# EsquematicoFonte.net
KiCad netlist of a schematic drawn in Altium Designer
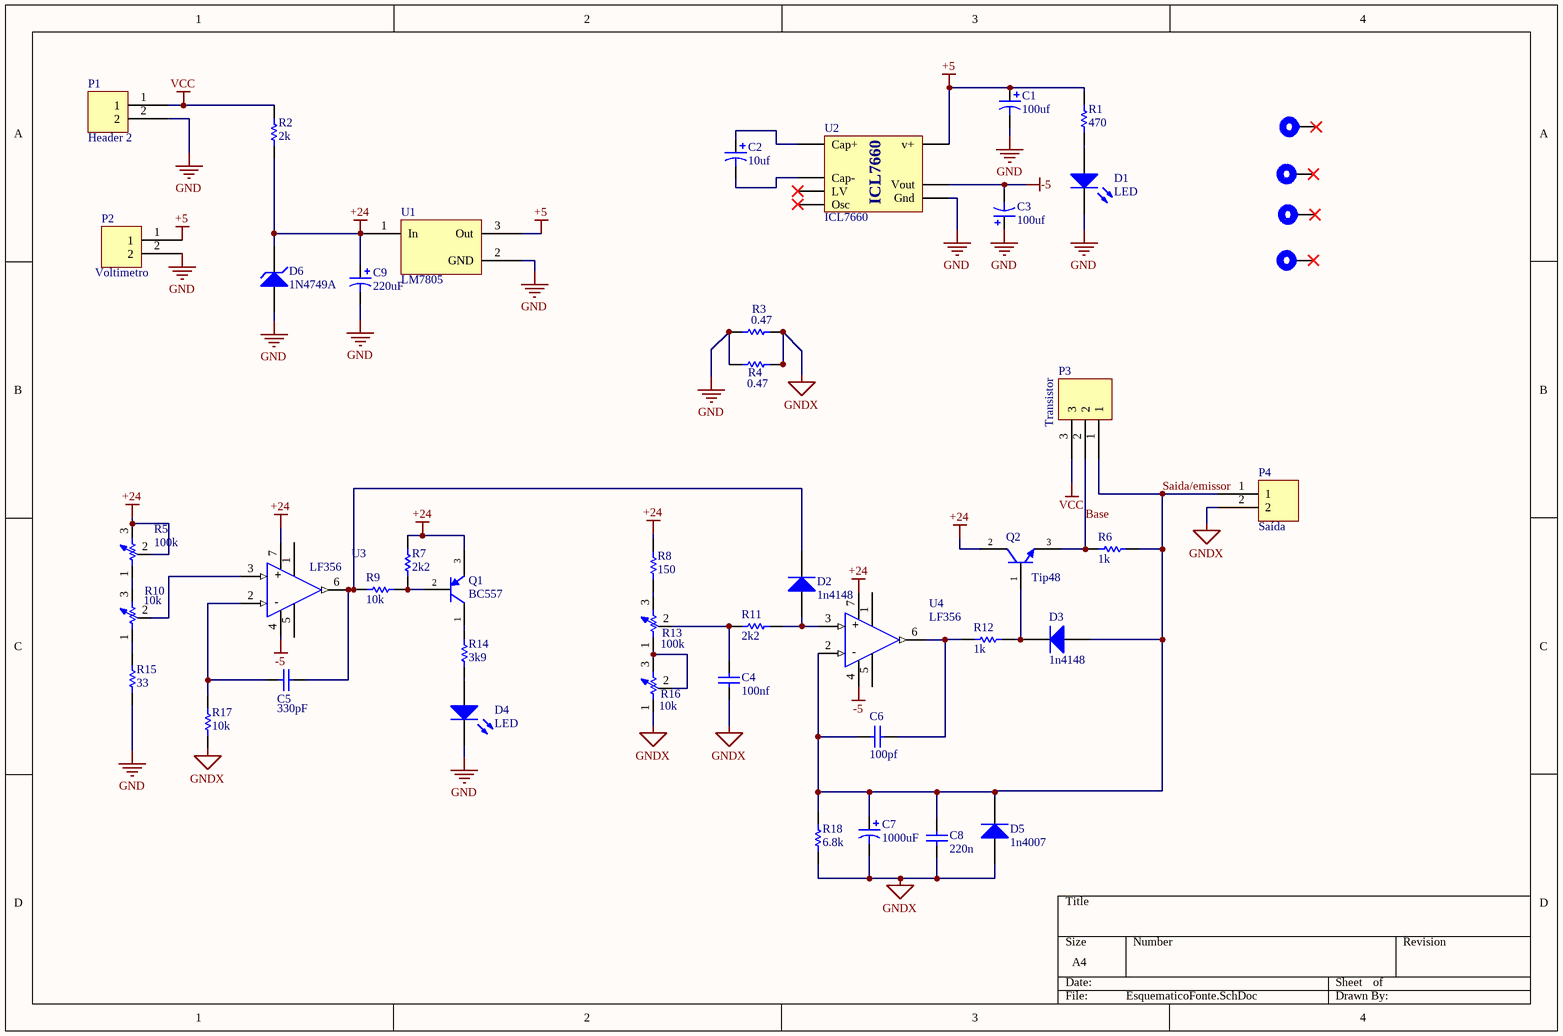
[diagram p0: EsquematicoFonte.SchDoc]

(export (version "E")
  (design (tool "Eeschema 10.0.6"))
  (components
    (comp (ref "C1")
      (value "100uf")
      (footprint "cap_rad_d6.3X11POL")
      (description "Polarized Capacitor")
      (libsource (lib "Basic Library") (part "CP"))
    )
    (comp (ref "C2")
      (value "10uf")
      (footprint "CAP_RAD_D5x11pol")
      (description "Polarized Capacitor")
      (libsource (lib "Basic Library") (part "CP"))
    )
    (comp (ref "C3")
      (value "100uf")
      (footprint "cap_rad_d6.3X11POL")
      (description "Polarized Capacitor")
      (libsource (lib "Basic Library") (part "CP"))
    )
    (comp (ref "C4")
      (value "100nf")
      (footprint "CAP_BOX_7.2x2.5x6.5_RD")
      (description "Capacitor")
      (libsource (lib "Basic Library") (part "C"))
    )
    (comp (ref "C5")
      (value "330pF")
      (footprint "CAP_BOX_7.2x2.5x6.5_RD")
      (description "Capacitor")
      (libsource (lib "Basic Library") (part "C"))
    )
    (comp (ref "C6")
      (value "100pf")
      (footprint "CAP_BOX_7.2x2.5x6.5_RD")
      (description "Capacitor")
      (libsource (lib "Basic Library") (part "C"))
    )
    (comp (ref "C7")
      (value "1000uF")
      (footprint "cap_rad_d10X12.5POL")
      (description "Polarized Capacitor")
      (libsource (lib "Basic Library") (part "CP"))
    )
    (comp (ref "C8")
      (value "220n")
      (footprint "CAP_BOX_7.2x2.5x6.5_RD")
      (description "Capacitor")
      (libsource (lib "Basic Library") (part "C"))
    )
    (comp (ref "C9")
      (value "220uF")
      (footprint "cap_rad_d10X12.5POL")
      (description "Polarized Capacitor")
      (libsource (lib "Basic Library") (part "CP"))
    )
    (comp (ref "D1") (value "LED") (footprint "LED_5MM_GREEN") (libsource (lib "Basic Library") (part "LED")))
    (comp (ref "D2")
      (value "1n4148")
      (footprint "DIODE-SIGNAL")
      (description "Diode")
      (libsource (lib "Basic Library") (part "D"))
    )
    (comp (ref "D3")
      (value "1n4148")
      (footprint "DIODE-SIGNAL")
      (description "Diode")
      (libsource (lib "Basic Library") (part "D"))
    )
    (comp (ref "D4") (value "LED") (footprint "LED_5MM_RED") (libsource (lib "Basic Library") (part "LED")))
    (comp (ref "D5")
      (value "1n4007")
      (footprint "DIODE-1N400X")
      (description "Diode")
      (libsource (lib "Basic Library") (part "D"))
    )
    (comp (ref "D6")
      (value "1N4749A")
      (footprint "DIODE-SIGNAL")
      (description "Zener Diode")
      (libsource (lib "Basic Library") (part "D Zener"))
    )
    (comp (ref "H1") (value "Hole") (footprint "HOLE_M3") (libsource (lib "Basic Library") (part "Hole")))
    (comp (ref "H2") (value "Hole") (footprint "HOLE_M3") (libsource (lib "Basic Library") (part "Hole")))
    (comp (ref "H3") (value "Hole") (footprint "HOLE_M3") (libsource (lib "Basic Library") (part "Hole")))
    (comp (ref "H4") (value "Hole") (footprint "HOLE_M3") (libsource (lib "Basic Library") (part "Hole")))
    (comp (ref "P1") (value "Header 2") (footprint "KRE-2") (libsource (lib "") (part "Header 2_1")))
    (comp (ref "P2") (value "Voltimetro") (footprint "KRE-2") (libsource (lib "") (part "Header 2_1")))
    (comp (ref "P3")
      (value "Transistor")
      (footprint "KRE-3")
      (libsource (lib "Connectores") (part "Header 3"))
    )
    (comp (ref "P4") (value "Saída") (footprint "KRE-2") (libsource (lib "Connectores") (part "Header 2")))
    (comp (ref "Q1")
      (value "BC557")
      (footprint "TO-92")
      (description "PNP Bipolar Transistor")
      (libsource (lib "Basic Library") (part "PNP"))
    )
    (comp (ref "Q2") (value "Tip48") (footprint "TIP48") (libsource (lib "BateriaLIB") (part "Tip48")))
    (comp (ref "R1")
      (value "470")
      (footprint "AXIAL-0.4")
      (description "Resistor")
      (libsource (lib "Symbols") (part "R"))
    )
    (comp (ref "R2")
      (value "2k")
      (footprint "AXIAL-0.4")
      (description "Resistor")
      (libsource (lib "Symbols") (part "R"))
    )
    (comp (ref "R3")
      (value "0.47")
      (footprint "resistor 5W")
      (description "Resistor")
      (libsource (lib "Symbols") (part "R"))
    )
    (comp (ref "R4")
      (value "0.47")
      (footprint "resistor 5W")
      (description "Resistor")
      (libsource (lib "Symbols") (part "R"))
    )
    (comp (ref "R5")
      (value "100k")
      (footprint "VR1")
      (description "Variable Resistor")
      (libsource (lib "Basic Library") (part "R Adj"))
    )
    (comp (ref "R6")
      (value "1k")
      (footprint "AXIAL-0.4")
      (description "Resistor")
      (libsource (lib "Symbols") (part "R"))
    )
    (comp (ref "R7")
      (value "2k2")
      (footprint "AXIAL-0.4")
      (description "Resistor")
      (libsource (lib "Symbols") (part "R"))
    )
    (comp (ref "R8")
      (value "150")
      (footprint "AXIAL-0.4")
      (description "Resistor")
      (libsource (lib "Symbols") (part "R"))
    )
    (comp (ref "R9")
      (value "10k")
      (footprint "AXIAL-0.4")
      (description "Resistor")
      (libsource (lib "Symbols") (part "R"))
    )
    (comp (ref "R10")
      (value "10k")
      (footprint "PotenciometroDeitado")
      (description "Variable Resistor")
      (libsource (lib "Basic Library") (part "R Adj"))
    )
    (comp (ref "R11")
      (value "2k2")
      (footprint "AXIAL-0.4")
      (description "Resistor")
      (libsource (lib "Symbols") (part "R"))
    )
    (comp (ref "R12")
      (value "1k")
      (footprint "AXIAL-0.4")
      (description "Resistor")
      (libsource (lib "Symbols") (part "R"))
    )
    (comp (ref "R13")
      (value "100k")
      (footprint "PotenciometroDeitado")
      (description "Variable Resistor")
      (libsource (lib "Basic Library") (part "R Adj"))
    )
    (comp (ref "R14")
      (value "3k9")
      (footprint "AXIAL-0.4")
      (description "Resistor")
      (libsource (lib "Symbols") (part "R"))
    )
    (comp (ref "R15")
      (value "33")
      (footprint "AXIAL-0.4")
      (description "Resistor")
      (libsource (lib "Symbols") (part "R"))
    )
    (comp (ref "R16")
      (value "10k")
      (footprint "PotenciometroDeitado")
      (description "Variable Resistor")
      (libsource (lib "Basic Library") (part "R Adj"))
    )
    (comp (ref "R17")
      (value "10k")
      (footprint "AXIAL-0.4")
      (description "Resistor")
      (libsource (lib "Symbols") (part "R"))
    )
    (comp (ref "R18")
      (value "6.8k")
      (footprint "AXIAL-0.4")
      (description "Resistor")
      (libsource (lib "Symbols") (part "R"))
    )
    (comp (ref "U1") (value "LM7805") (footprint "LM7805") (libsource (lib "BateriaLIB") (part "LM7805")))
    (comp (ref "U2") (value "ICL7660") (footprint "ICL7660") (libsource (lib "BateriaLIB") (part "ICL7660")))
    (comp (ref "U3") (value "LF356") (footprint "LF356") (libsource (lib "BateriaLIB") (part "LF356")))
    (comp (ref "U4") (value "LF356") (footprint "LF356") (libsource (lib "BateriaLIB") (part "LF356")))
  )
  (nets
    (net (code "1") (name "+5") (class "Default")
      (node (ref "C1") (pin "1") (pinfunction "1_1") (pintype "passive"))
      (node (ref "P2") (pin "1") (pinfunction "1_1") (pintype "passive"))
      (node (ref "R1") (pin "1") (pinfunction "1_1") (pintype "passive"))
      (node (ref "U1") (pin "3") (pinfunction "Out_3") (pintype "passive"))
      (node (ref "U2") (pin "8") (pinfunction "v+_8") (pintype "passive"))
    )
    (net (code "2") (name "+24") (class "Default")
      (node (ref "C9") (pin "1") (pinfunction "1_1") (pintype "passive"))
      (node (ref "D6") (pin "2") (pinfunction "K_2") (pintype "passive"))
      (node (ref "Q1") (pin "3") (pinfunction "E_3") (pintype "passive"))
      (node (ref "Q2") (pin "2") (pinfunction "C_2") (pintype "passive"))
      (node (ref "R2") (pin "2") (pinfunction "2_2") (pintype "passive"))
      (node (ref "R5") (pin "2") (pinfunction "2_2") (pintype "passive"))
      (node (ref "R5") (pin "3") (pinfunction "3_3") (pintype "passive"))
      (node (ref "R7") (pin "1") (pinfunction "1_1") (pintype "passive"))
      (node (ref "R8") (pin "1") (pinfunction "1_1") (pintype "passive"))
      (node (ref "U1") (pin "1") (pinfunction "In_1") (pintype "passive"))
      (node (ref "U3") (pin "7") (pinfunction "7_7") (pintype "passive"))
      (node (ref "U4") (pin "7") (pinfunction "7_7") (pintype "passive"))
    )
    (net (code "3") (name "-5") (class "Default")
      (node (ref "C3") (pin "2") (pinfunction "2_2") (pintype "passive"))
      (node (ref "U2") (pin "5") (pinfunction "Vout_5") (pintype "passive"))
      (node (ref "U3") (pin "4") (pinfunction "4_4") (pintype "passive"))
      (node (ref "U4") (pin "4") (pinfunction "4_4") (pintype "passive"))
    )
    (net (code "4") (name "/Base") (class "Default")
      (node (ref "P3") (pin "2") (pinfunction "2_2") (pintype "passive"))
      (node (ref "Q2") (pin "3") (pinfunction "E_3") (pintype "passive"))
      (node (ref "R6") (pin "1") (pinfunction "1_1") (pintype "passive"))
    )
    (net (code "5") (name "/Saida{slash}emissor") (class "Default")
      (node (ref "C6") (pin "2") (pinfunction "2_2") (pintype "passive"))
      (node (ref "C7") (pin "1") (pinfunction "1_1") (pintype "passive"))
      (node (ref "C8") (pin "1") (pinfunction "1_1") (pintype "passive"))
      (node (ref "D3") (pin "1") (pinfunction "A_1") (pintype "passive"))
      (node (ref "D5") (pin "2") (pinfunction "K_2") (pintype "passive"))
      (node (ref "P3") (pin "1") (pinfunction "1_1") (pintype "passive"))
      (node (ref "P4") (pin "1") (pinfunction "1_1") (pintype "passive"))
      (node (ref "R18") (pin "2") (pinfunction "2_2") (pintype "passive"))
      (node (ref "R6") (pin "2") (pinfunction "2_2") (pintype "passive"))
      (node (ref "U4") (pin "2") (pinfunction "-_2") (pintype "input"))
    )
    (net (code "6") (name "GND") (class "Default")
      (node (ref "C1") (pin "2") (pinfunction "2_2") (pintype "passive"))
      (node (ref "C3") (pin "1") (pinfunction "1_1") (pintype "passive"))
      (node (ref "C9") (pin "2") (pinfunction "2_2") (pintype "passive"))
      (node (ref "D1") (pin "2") (pinfunction "K_2") (pintype "passive"))
      (node (ref "D4") (pin "2") (pinfunction "K_2") (pintype "passive"))
      (node (ref "D6") (pin "1") (pinfunction "A_1") (pintype "passive"))
      (node (ref "P1") (pin "2") (pinfunction "2_2") (pintype "passive"))
      (node (ref "P2") (pin "2") (pinfunction "2_2") (pintype "passive"))
      (node (ref "R15") (pin "2") (pinfunction "2_2") (pintype "passive"))
      (node (ref "R3") (pin "1") (pinfunction "1_1") (pintype "passive"))
      (node (ref "R4") (pin "1") (pinfunction "1_1") (pintype "passive"))
      (node (ref "U1") (pin "2") (pinfunction "GND_2") (pintype "passive"))
      (node (ref "U2") (pin "3") (pinfunction "Gnd_3") (pintype "passive"))
    )
    (net (code "7") (name "GNDX") (class "Default")
      (node (ref "C4") (pin "1") (pinfunction "1_1") (pintype "passive"))
      (node (ref "C7") (pin "2") (pinfunction "2_2") (pintype "passive"))
      (node (ref "C8") (pin "2") (pinfunction "2_2") (pintype "passive"))
      (node (ref "D5") (pin "1") (pinfunction "A_1") (pintype "passive"))
      (node (ref "P4") (pin "2") (pinfunction "2_2") (pintype "passive"))
      (node (ref "R16") (pin "1") (pinfunction "1_1") (pintype "passive"))
      (node (ref "R17") (pin "2") (pinfunction "2_2") (pintype "passive"))
      (node (ref "R18") (pin "1") (pinfunction "1_1") (pintype "passive"))
      (node (ref "R3") (pin "2") (pinfunction "2_2") (pintype "passive"))
      (node (ref "R4") (pin "2") (pinfunction "2_2") (pintype "passive"))
    )
    (net (code "8") (name "Net-(C4-Pad2)") (class "Default")
      (node (ref "C4") (pin "2") (pinfunction "2_2") (pintype "passive"))
      (node (ref "R11") (pin "1") (pinfunction "1_1") (pintype "passive"))
      (node (ref "R13") (pin "2") (pinfunction "2_2") (pintype "passive"))
    )
    (net (code "9") (name "Net-(D1-A)") (class "Default")
      (node (ref "D1") (pin "1") (pinfunction "A_1") (pintype "passive"))
      (node (ref "R1") (pin "2") (pinfunction "2_2") (pintype "passive"))
    )
    (net (code "10") (name "Net-(D2-A)") (class "Default")
      (node (ref "D2") (pin "1") (pinfunction "A_1") (pintype "passive"))
      (node (ref "R11") (pin "2") (pinfunction "2_2") (pintype "passive"))
      (node (ref "U4") (pin "3") (pinfunction "VIN_3") (pintype "input"))
    )
    (net (code "11") (name "Net-(D2-K)") (class "Default")
      (node (ref "C5") (pin "2") (pinfunction "2_2") (pintype "passive"))
      (node (ref "D2") (pin "2") (pinfunction "K_2") (pintype "passive"))
      (node (ref "R9") (pin "1") (pinfunction "1_1") (pintype "passive"))
      (node (ref "U3") (pin "6") (pinfunction "VOUT_6") (pintype "output"))
    )
    (net (code "12") (name "Net-(D3-K)") (class "Default")
      (node (ref "D3") (pin "2") (pinfunction "K_2") (pintype "passive"))
      (node (ref "Q2") (pin "1") (pinfunction "B_1") (pintype "passive"))
      (node (ref "R12") (pin "2") (pinfunction "2_2") (pintype "passive"))
    )
    (net (code "13") (name "Net-(D4-A)") (class "Default")
      (node (ref "D4") (pin "1") (pinfunction "A_1") (pintype "passive"))
      (node (ref "R14") (pin "2") (pinfunction "2_2") (pintype "passive"))
    )
    (net (code "14") (name "Net-(Q1-B)") (class "Default")
      (node (ref "Q1") (pin "2") (pinfunction "B_2") (pintype "passive"))
      (node (ref "R7") (pin "2") (pinfunction "2_2") (pintype "passive"))
      (node (ref "R9") (pin "2") (pinfunction "2_2") (pintype "passive"))
    )
    (net (code "15") (name "Net-(Q1-C)") (class "Default")
      (node (ref "Q1") (pin "1") (pinfunction "C_1") (pintype "passive"))
      (node (ref "R14") (pin "1") (pinfunction "1_1") (pintype "passive"))
    )
    (net (code "16") (name "Net-(R10-Pad1)") (class "Default")
      (node (ref "R10") (pin "1") (pinfunction "1_1") (pintype "passive"))
      (node (ref "R15") (pin "1") (pinfunction "1_1") (pintype "passive"))
    )
    (net (code "17") (name "Net-(R10-Pad3)") (class "Default")
      (node (ref "R10") (pin "3") (pinfunction "3_3") (pintype "passive"))
      (node (ref "R5") (pin "1") (pinfunction "1_1") (pintype "passive"))
    )
    (net (code "18") (name "Net-(R13-Pad1)") (class "Default")
      (node (ref "R13") (pin "1") (pinfunction "1_1") (pintype "passive"))
      (node (ref "R16") (pin "2") (pinfunction "2_2") (pintype "passive"))
      (node (ref "R16") (pin "3") (pinfunction "3_3") (pintype "passive"))
    )
    (net (code "19") (name "Net-(R13-Pad3)") (class "Default")
      (node (ref "R13") (pin "3") (pinfunction "3_3") (pintype "passive"))
      (node (ref "R8") (pin "2") (pinfunction "2_2") (pintype "passive"))
    )
    (net (code "20") (name "Net-(U2-Cap+)") (class "Default")
      (node (ref "C2") (pin "1") (pinfunction "1_1") (pintype "passive"))
      (node (ref "U2") (pin "2") (pinfunction "Cap+_2") (pintype "passive"))
    )
    (net (code "21") (name "Net-(U2-Cap-)") (class "Default")
      (node (ref "C2") (pin "2") (pinfunction "2_2") (pintype "passive"))
      (node (ref "U2") (pin "4") (pinfunction "Cap-_4") (pintype "passive"))
    )
    (net (code "22") (name "Net-(U3--)") (class "Default")
      (node (ref "C5") (pin "1") (pinfunction "1_1") (pintype "passive"))
      (node (ref "R17") (pin "1") (pinfunction "1_1") (pintype "passive"))
      (node (ref "U3") (pin "2") (pinfunction "-_2") (pintype "input"))
    )
    (net (code "23") (name "Net-(U3-VIN)") (class "Default")
      (node (ref "R10") (pin "2") (pinfunction "2_2") (pintype "passive"))
      (node (ref "U3") (pin "3") (pinfunction "VIN_3") (pintype "input"))
    )
    (net (code "24") (name "Net-(U4-VOUT)") (class "Default")
      (node (ref "C6") (pin "1") (pinfunction "1_1") (pintype "passive"))
      (node (ref "R12") (pin "1") (pinfunction "1_1") (pintype "passive"))
      (node (ref "U4") (pin "6") (pinfunction "VOUT_6") (pintype "output"))
    )
    (net (code "25") (name "VCC") (class "Default")
      (node (ref "P1") (pin "1") (pinfunction "1_1") (pintype "passive"))
      (node (ref "P3") (pin "3") (pinfunction "3_3") (pintype "passive"))
      (node (ref "R2") (pin "1") (pinfunction "1_1") (pintype "passive"))
    )
    (net (code "26") (name "unconnected-(H1-Pad1)") (class "Default")
      (node (ref "H1") (pin "1") (pinfunction "1_1") (pintype "passive+no_connect"))
    )
    (net (code "27") (name "unconnected-(H2-Pad1)") (class "Default")
      (node (ref "H2") (pin "1") (pinfunction "1_1") (pintype "passive+no_connect"))
    )
    (net (code "28") (name "unconnected-(H3-Pad1)") (class "Default")
      (node (ref "H3") (pin "1") (pinfunction "1_1") (pintype "passive+no_connect"))
    )
    (net (code "29") (name "unconnected-(H4-Pad1)") (class "Default")
      (node (ref "H4") (pin "1") (pinfunction "1_1") (pintype "passive+no_connect"))
    )
    (net (code "30") (name "unconnected-(U2-LV-Pad6)") (class "Default")
      (node (ref "U2") (pin "6") (pinfunction "LV_6") (pintype "passive+no_connect"))
    )
    (net (code "31") (name "unconnected-(U2-Osc-Pad7)") (class "Default")
      (node (ref "U2") (pin "7") (pinfunction "Osc_7") (pintype "passive+no_connect"))
    )
    (net (code "32") (name "unconnected-(U3-Pad1)") (class "Default")
      (node (ref "U3") (pin "1") (pinfunction "1_1") (pintype "passive"))
    )
    (net (code "33") (name "unconnected-(U3-Pad5)") (class "Default")
      (node (ref "U3") (pin "5") (pinfunction "5_5") (pintype "passive"))
    )
    (net (code "34") (name "unconnected-(U4-Pad1)") (class "Default")
      (node (ref "U4") (pin "1") (pinfunction "1_1") (pintype "passive"))
    )
    (net (code "35") (name "unconnected-(U4-Pad5)") (class "Default")
      (node (ref "U4") (pin "5") (pinfunction "5_5") (pintype "passive"))
    )
  )
)
